# PIC32MX220F032B.net
KiCad netlist of a schematic drawn in Altium Designer
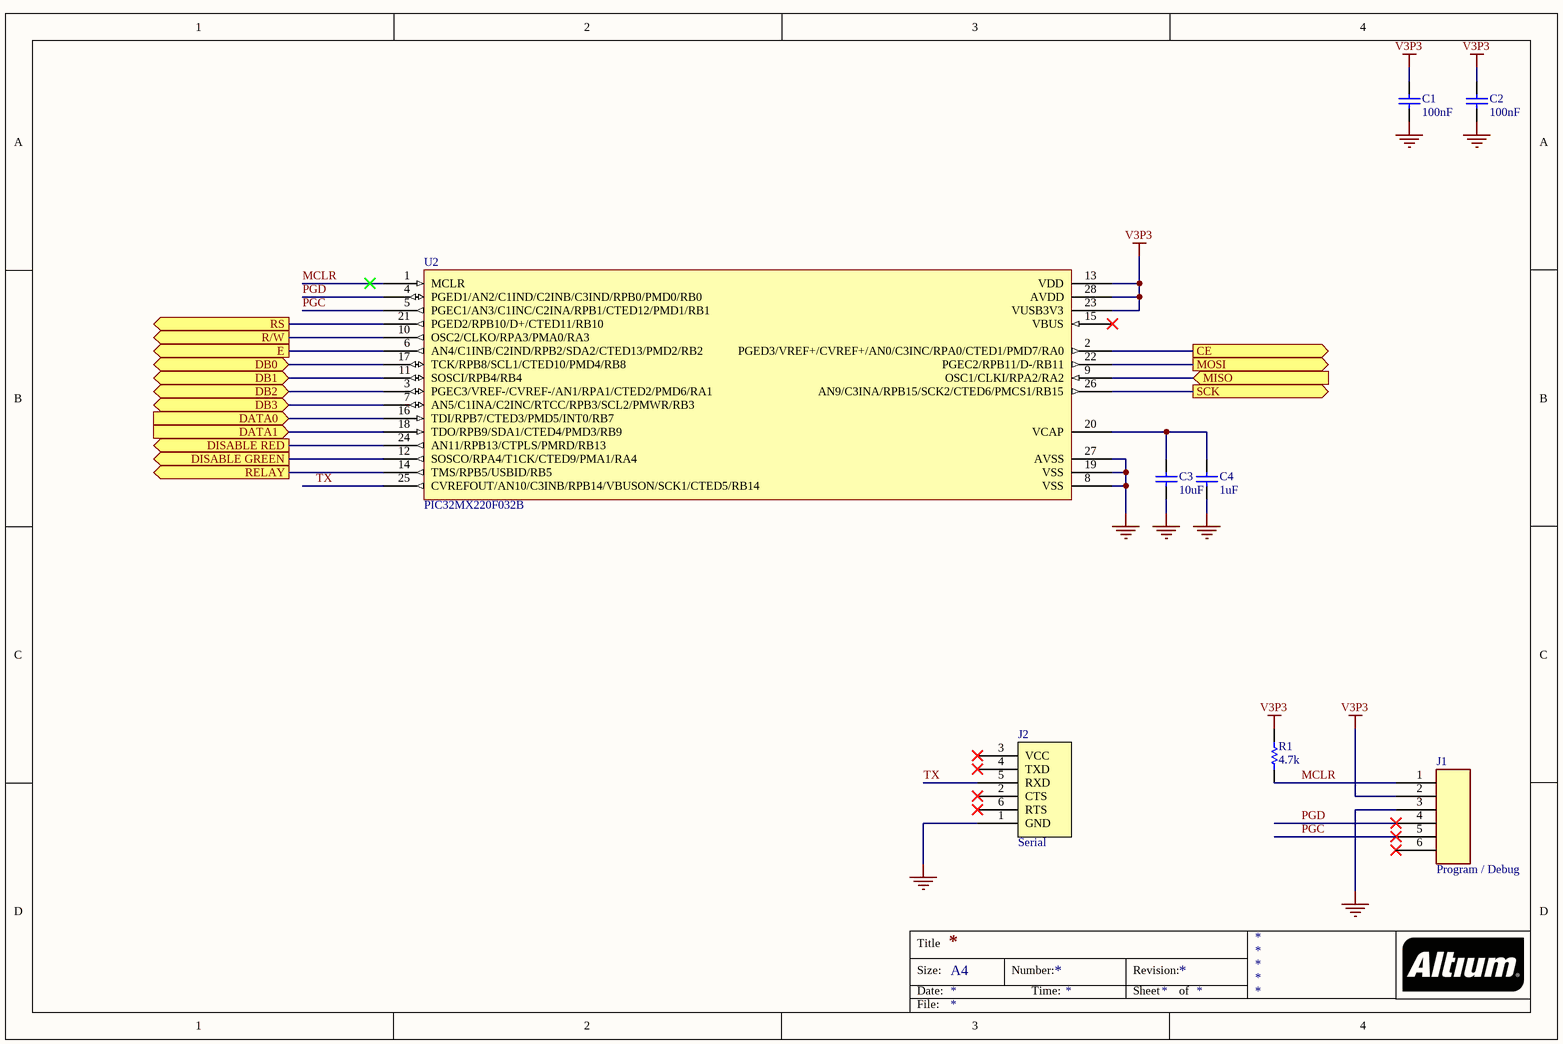
[diagram p0: PIC32MX220F032B.SchDoc]

(export (version "E")
  (design (tool "Eeschema 10.0.6"))
  (components
    (comp (ref "C1")
      (value "100nF")
      (footprint "CAP 0603")
      (description "Capacitor")
      (fields (field (name "PUBLISHER") "Altium Limited"))
      (libsource (lib "Miscellaneous Devices") (part "Cap"))
    )
    (comp (ref "C2")
      (value "100nF")
      (footprint "CAP 0603")
      (description "Capacitor")
      (fields (field (name "PUBLISHER") "Altium Limited"))
      (libsource (lib "Miscellaneous Devices") (part "Cap"))
    )
    (comp (ref "C3")
      (value "10uF")
      (footprint "CAP 0603")
      (description "Capacitor")
      (fields (field (name "PUBLISHER") "Altium Limited"))
      (libsource (lib "Miscellaneous Devices") (part "Cap"))
    )
    (comp (ref "C4")
      (value "1uF")
      (footprint "CAP 0603")
      (description "Capacitor")
      (fields (field (name "PUBLISHER") "Altium Limited"))
      (libsource (lib "Miscellaneous Devices") (part "Cap"))
    )
    (comp (ref "J1")
      (value "Program / Debug")
      (footprint "RJ12_90")
      (description "RJ11")
      (libsource (lib "Schlib1") (part "Debug"))
    )
    (comp (ref "J2")
      (value "Serial")
      (footprint "Header 6 pin")
      (description "Header 6 pin")
      (libsource (lib "Card_reader") (part "Serial"))
    )
    (comp (ref "R1")
      (value "4.7k")
      (footprint "RES 0603")
      (description "Resistor")
      (fields (field (name "PUBLISHER") "Altium Limited"))
      (libsource (lib "Miscellaneous Devices") (part "Res1"))
    )
    (comp (ref "U2")
      (value "PIC32MX220F032B")
      (footprint "SOIC (28)")
      (libsource (lib "Card_reader") (part "PIC32MX220F032B"))
    )
  )
  (nets
    (net (code "1") (name "/CE") (class "Default")
      (node (ref "U2") (pin "2") (pinfunction "PGED3/VREF+/CVREF+/AN0/C3INC/RPA0/CTED1/PMD7/RA0_2") (pintype "output"))
    )
    (net (code "2") (name "/DATA0") (class "Default")
      (node (ref "U2") (pin "16") (pinfunction "TDI/RPB7/CTED3/PMD5/INT0/RB7_16") (pintype "input"))
    )
    (net (code "3") (name "/DATA1") (class "Default")
      (node (ref "U2") (pin "18") (pinfunction "TDO/RPB9/SDA1/CTED4/PMD3/RB9_18") (pintype "input"))
    )
    (net (code "4") (name "/DB0") (class "Default")
      (node (ref "U2") (pin "17") (pinfunction "TCK/RPB8/SCL1/CTED10/PMD4/RB8_17") (pintype "bidirectional"))
    )
    (net (code "5") (name "/DB1") (class "Default")
      (node (ref "U2") (pin "11") (pinfunction "SOSCI/RPB4/RB4_11") (pintype "bidirectional"))
    )
    (net (code "6") (name "/DB2") (class "Default")
      (node (ref "U2") (pin "3") (pinfunction "PGEC3/VREF-/CVREF-/AN1/RPA1/CTED2/PMD6/RA1_3") (pintype "bidirectional"))
    )
    (net (code "7") (name "/DB3") (class "Default")
      (node (ref "U2") (pin "7") (pinfunction "AN5/C1INA/C2INC/RTCC/RPB3/SCL2/PMWR/RB3_7") (pintype "bidirectional"))
    )
    (net (code "8") (name "/DISABLE GREEN") (class "Default")
      (node (ref "U2") (pin "12") (pinfunction "SOSCO/RPA4/T1CK/CTED9/PMA1/RA4_12") (pintype "output"))
    )
    (net (code "9") (name "/DISABLE RED") (class "Default")
      (node (ref "U2") (pin "24") (pinfunction "AN11/RPB13/CTPLS/PMRD/RB13_24") (pintype "output"))
    )
    (net (code "10") (name "/E") (class "Default")
      (node (ref "U2") (pin "6") (pinfunction "AN4/C1INB/C2IND/RPB2/SDA2/CTED13/PMD2/RB2_6") (pintype "output"))
    )
    (net (code "11") (name "/MCLR") (class "Default")
      (node (ref "J1") (pin "1") (pintype "passive"))
      (node (ref "R1") (pin "1") (pinfunction "1_1") (pintype "passive"))
      (node (ref "U2") (pin "1") (pinfunction "MCLR_1") (pintype "input"))
    )
    (net (code "12") (name "/MISO") (class "Default")
      (node (ref "U2") (pin "9") (pinfunction "OSC1/CLKI/RPA2/RA2_9") (pintype "input"))
    )
    (net (code "13") (name "/MOSI") (class "Default")
      (node (ref "U2") (pin "22") (pinfunction "PGEC2/RPB11/D-/RB11_22") (pintype "output"))
    )
    (net (code "14") (name "/PGC") (class "Default")
      (node (ref "J1") (pin "5") (pinfunction "68_5") (pintype "passive"))
      (node (ref "U2") (pin "5") (pinfunction "PGEC1/AN3/C1INC/C2INA/RPB1/CTED12/PMD1/RB1_5") (pintype "output"))
    )
    (net (code "15") (name "/PGD") (class "Default")
      (node (ref "J1") (pin "4") (pinfunction "67_4") (pintype "passive"))
      (node (ref "U2") (pin "4") (pinfunction "PGED1/AN2/C1IND/C2INB/C3IND/RPB0/PMD0/RB0_4") (pintype "bidirectional"))
    )
    (net (code "16") (name "/RELAY") (class "Default")
      (node (ref "U2") (pin "14") (pinfunction "TMS/RPB5/USBID/RB5_14") (pintype "output"))
    )
    (net (code "17") (name "/RS") (class "Default")
      (node (ref "U2") (pin "21") (pinfunction "PGED2/RPB10/D+/CTED11/RB10_21") (pintype "output"))
    )
    (net (code "18") (name "/R{slash}W") (class "Default")
      (node (ref "U2") (pin "10") (pinfunction "OSC2/CLKO/RPA3/PMA0/RA3_10") (pintype "output"))
    )
    (net (code "19") (name "/SCK") (class "Default")
      (node (ref "U2") (pin "26") (pinfunction "AN9/C3INA/RPB15/SCK2/CTED6/PMCS1/RB15_26") (pintype "output"))
    )
    (net (code "20") (name "/TX") (class "Default")
      (node (ref "J2") (pin "5") (pinfunction "RXD_5") (pintype "passive"))
      (node (ref "U2") (pin "25") (pinfunction "CVREFOUT/AN10/C3INB/RPB14/VBUSON/SCK1/CTED5/RB14_25") (pintype "output"))
    )
    (net (code "21") (name "GND") (class "Default")
      (node (ref "C1") (pin "1") (pinfunction "1_1") (pintype "passive"))
      (node (ref "C2") (pin "1") (pinfunction "1_1") (pintype "passive"))
      (node (ref "C3") (pin "1") (pinfunction "1_1") (pintype "passive"))
      (node (ref "C4") (pin "2") (pinfunction "2_2") (pintype "passive"))
      (node (ref "J1") (pin "3") (pintype "passive"))
      (node (ref "J2") (pin "1") (pinfunction "GND_1") (pintype "passive"))
      (node (ref "U2") (pin "19") (pinfunction "VSS_19") (pintype "passive"))
      (node (ref "U2") (pin "27") (pinfunction "AVSS_27") (pintype "passive"))
      (node (ref "U2") (pin "8") (pinfunction "VSS_8") (pintype "passive"))
    )
    (net (code "22") (name "Net-(U2-VCAP)") (class "Default")
      (node (ref "C3") (pin "2") (pinfunction "2_2") (pintype "passive"))
      (node (ref "C4") (pin "1") (pinfunction "1_1") (pintype "passive"))
      (node (ref "U2") (pin "20") (pinfunction "VCAP_20") (pintype "passive"))
    )
    (net (code "23") (name "V3P3") (class "Default")
      (node (ref "C1") (pin "2") (pinfunction "2_2") (pintype "passive"))
      (node (ref "C2") (pin "2") (pinfunction "2_2") (pintype "passive"))
      (node (ref "J1") (pin "2") (pinfunction "65_2") (pintype "passive"))
      (node (ref "R1") (pin "2") (pinfunction "2_2") (pintype "passive"))
      (node (ref "U2") (pin "13") (pinfunction "VDD_13") (pintype "passive"))
      (node (ref "U2") (pin "23") (pinfunction "VUSB3V3_23") (pintype "power_in"))
      (node (ref "U2") (pin "28") (pinfunction "AVDD_28") (pintype "passive"))
    )
    (net (code "24") (name "unconnected-(J1-69-Pad6)") (class "Default")
      (node (ref "J1") (pin "6") (pinfunction "69_6") (pintype "power_in+no_connect"))
    )
    (net (code "25") (name "unconnected-(J2-CTS-Pad2)") (class "Default")
      (node (ref "J2") (pin "2") (pinfunction "CTS_2") (pintype "passive+no_connect"))
    )
    (net (code "26") (name "unconnected-(J2-RTS-Pad6)") (class "Default")
      (node (ref "J2") (pin "6") (pinfunction "RTS_6") (pintype "passive+no_connect"))
    )
    (net (code "27") (name "unconnected-(J2-TXD-Pad4)") (class "Default")
      (node (ref "J2") (pin "4") (pinfunction "TXD_4") (pintype "passive+no_connect"))
    )
    (net (code "28") (name "unconnected-(J2-VCC-Pad3)") (class "Default")
      (node (ref "J2") (pin "3") (pinfunction "VCC_3") (pintype "passive+no_connect"))
    )
    (net (code "29") (name "unconnected-(U2-VBUS-Pad15)") (class "Default")
      (node (ref "U2") (pin "15") (pinfunction "VBUS_15") (pintype "input+no_connect"))
    )
  )
)
